# SparkoStat.net
KiCad netlist of a schematic drawn in EAGLE
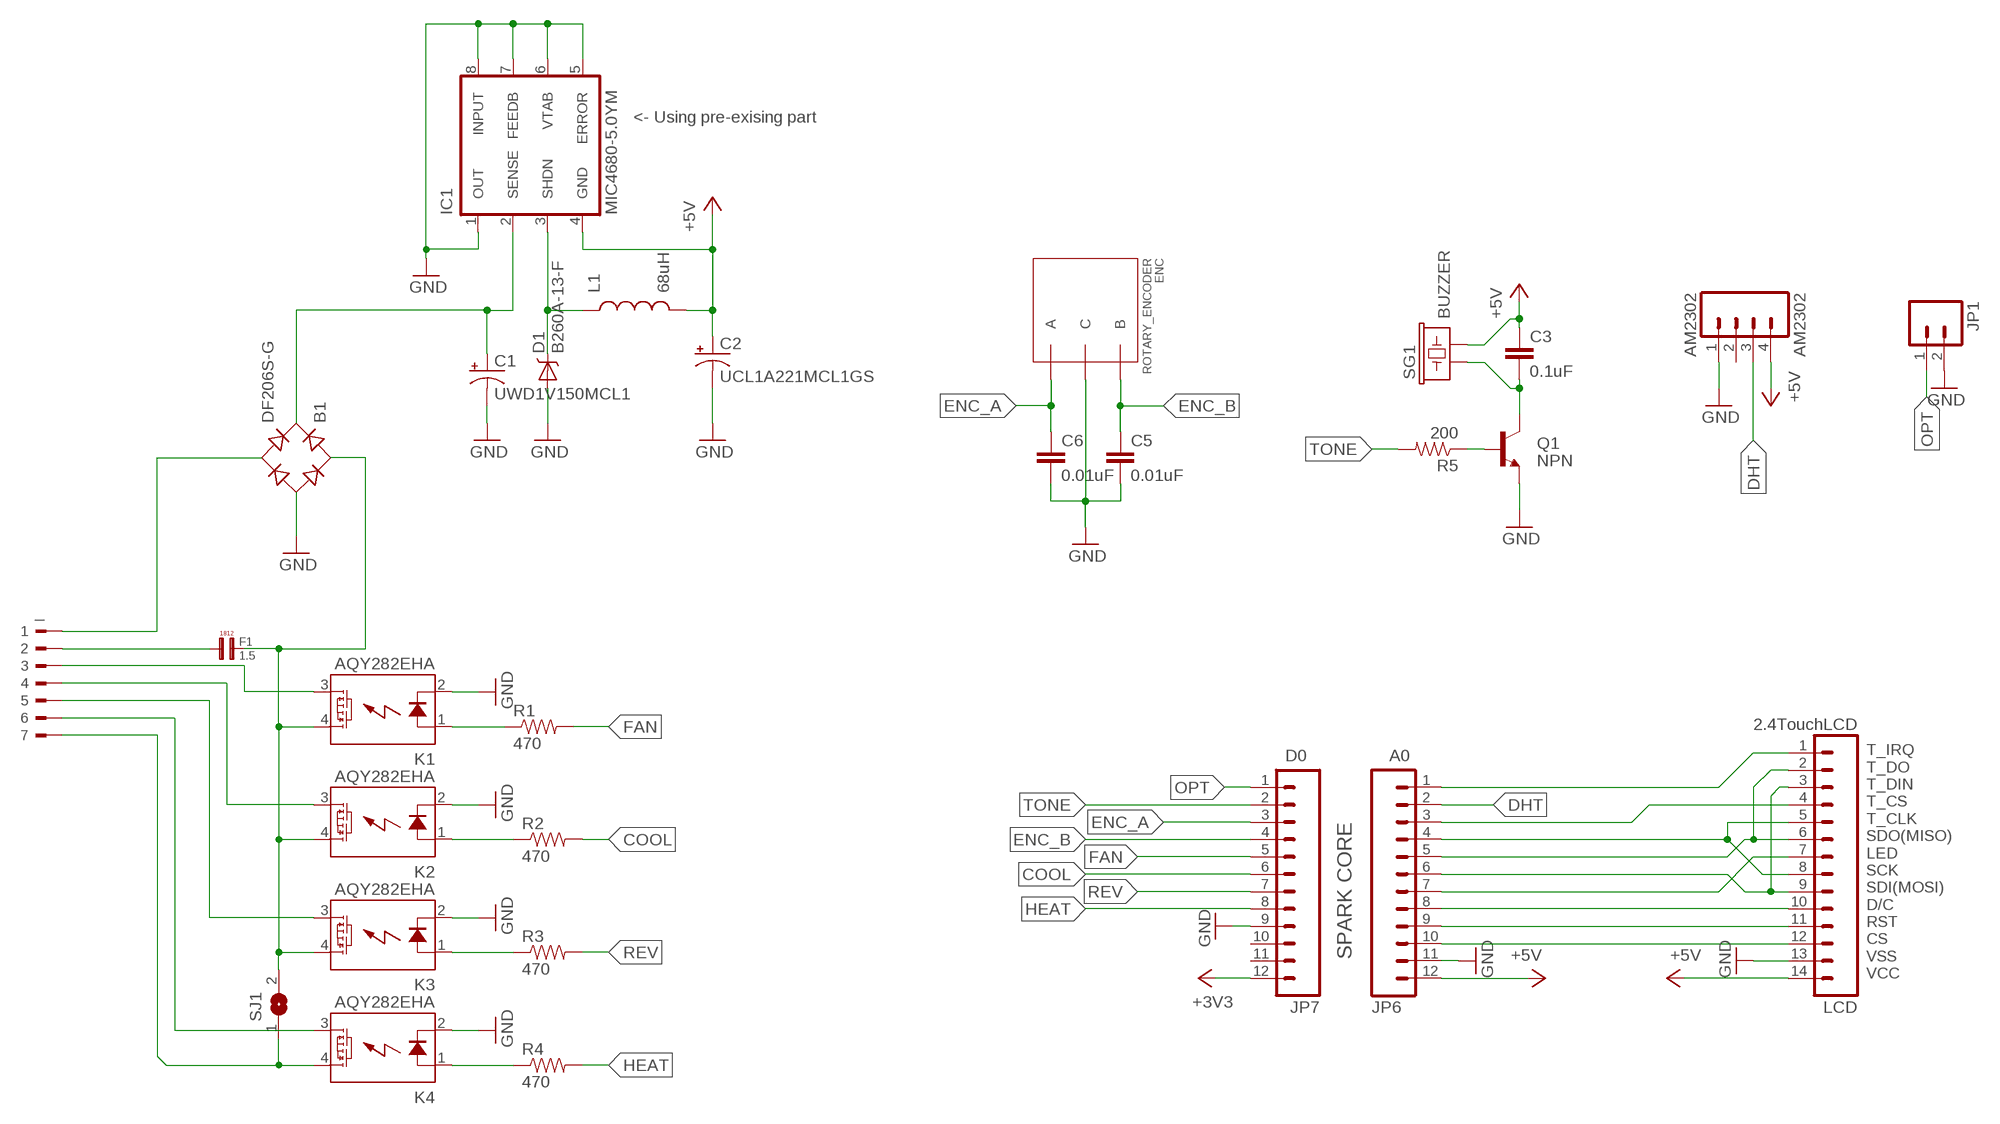
[diagram p0: schematic, sheet 1]

(export (version "E")
  (design (tool "Eeschema 10.0.6"))
  (components
    (comp (ref "AM2302")
      (value "AM2302")
      (footprint "eagle-import:1X04")
      (libsource (lib "eagle-import") (part "M04PTH"))
    )
    (comp (ref "B1")
      (value "DF206S-G")
      (footprint "eagle-import:DFS")
      (libsource (lib "eagle-import") (part "DFS01"))
    )
    (comp (ref "C1")
      (value "UWD1V150MCL1")
      (footprint "eagle-import:PANASONIC_C")
      (libsource (lib "eagle-import") (part "CAP_POLC"))
    )
    (comp (ref "C2")
      (value "UCL1A221MCL1GS")
      (footprint "eagle-import:PANASONIC_D")
      (libsource (lib "eagle-import") (part "CAP_POLD"))
    )
    (comp (ref "C3")
      (value "0.1uF")
      (footprint "eagle-import:0805")
      (libsource (lib "eagle-import") (part "CAP0805"))
    )
    (comp (ref "C5")
      (value "0.01uF")
      (footprint "eagle-import:0805")
      (libsource (lib "eagle-import") (part "CAP0805"))
    )
    (comp (ref "C6")
      (value "0.01uF")
      (footprint "eagle-import:0805")
      (libsource (lib "eagle-import") (part "CAP0805"))
    )
    (comp (ref "D1")
      (value "B260A-13-F")
      (footprint "eagle-import:SMA-DIODE")
      (libsource (lib "eagle-import") (part "DIODE-SCHOTTKY_"))
    )
    (comp (ref "ENC")
      (value "ROTARY_ENCODER")
      (footprint "eagle-import:ROTORY_ENC")
      (libsource (lib "eagle-import") (part "ROTARY_ENCODER"))
    )
    (comp (ref "F1")
      (value "1.5")
      (footprint "eagle-import:L4,8")
      (libsource (lib "eagle-import") (part "0,1ÂµF"))
    )
    (comp (ref "IC1")
      (value "MIC4680-5.0YM")
      (footprint "eagle-import:SO-08")
      (libsource (lib "eagle-import") (part "LP2951?ACM"))
    )
    (comp (ref "JP1")
      (value "M02PTH")
      (footprint "eagle-import:1X02")
      (libsource (lib "eagle-import") (part "M02PTH"))
    )
    (comp (ref "JP6")
      (value "M12LOCK")
      (footprint "eagle-import:1X12_LOCK")
      (libsource (lib "eagle-import") (part "M12LOCK"))
    )
    (comp (ref "JP7")
      (value "M12LOCK")
      (footprint "eagle-import:1X12_LOCK")
      (libsource (lib "eagle-import") (part "M12LOCK"))
    )
    (comp (ref "K1")
      (value "AQY282EHA")
      (footprint "eagle-import:SOP04")
      (libsource (lib "eagle-import") (part "AQYSOP22"))
    )
    (comp (ref "K2")
      (value "AQY282EHA")
      (footprint "eagle-import:SOP04")
      (libsource (lib "eagle-import") (part "AQYSOP22"))
    )
    (comp (ref "K3")
      (value "AQY282EHA")
      (footprint "eagle-import:SOP04")
      (libsource (lib "eagle-import") (part "AQYSOP22"))
    )
    (comp (ref "K4")
      (value "AQY282EHA")
      (footprint "eagle-import:SOP04")
      (libsource (lib "eagle-import") (part "AQYSOP22"))
    )
    (comp (ref "L1")
      (value "68uH")
      (footprint "eagle-import:DR1030")
      (libsource (lib "eagle-import") (part "INDUCTORDR1030"))
    )
    (comp (ref "LCD")
      (value "2.4TouchLCD")
      (footprint "eagle-import:1X14_LOCK")
      (libsource (lib "eagle-import") (part "M14LOCK"))
    )
    (comp (ref "Q1")
      (value "NPN")
      (footprint "eagle-import:SOT23")
      (libsource (lib "eagle-import") (part "TRANSISTOR_NPNSOT23"))
    )
    (comp (ref "R1")
      (value "470")
      (footprint "eagle-import:0805")
      (libsource (lib "eagle-import") (part "RESISTOR0805-RES"))
    )
    (comp (ref "R2")
      (value "470")
      (footprint "eagle-import:0805")
      (libsource (lib "eagle-import") (part "RESISTOR0805-RES"))
    )
    (comp (ref "R3")
      (value "470")
      (footprint "eagle-import:0805")
      (libsource (lib "eagle-import") (part "RESISTOR0805-RES"))
    )
    (comp (ref "R4")
      (value "470")
      (footprint "eagle-import:0805")
      (libsource (lib "eagle-import") (part "RESISTOR0805-RES"))
    )
    (comp (ref "R5")
      (value "200")
      (footprint "eagle-import:0805")
      (libsource (lib "eagle-import") (part "RESISTOR0805-RES"))
    )
    (comp (ref "SG1")
      (value "BUZZER")
      (footprint "eagle-import:BUZZER-12MM-NS")
      (libsource (lib "eagle-import") (part "BUZZERNS"))
    )
    (comp (ref "SJ1") (value "SJ") (footprint "eagle-import:SJ") (libsource (lib "eagle-import") (part "SJ")))
    (comp (ref "_")
      (value "180-7")
      (footprint "eagle-import:180-7")
      (libsource (lib "eagle-import") (part "180-7"))
    )
  )
  (nets
    (net (code "1") (name "+3V3") (class "Default")
      (node (ref "JP7") (pin "12") (pinfunction "12_12") (pintype "passive"))
    )
    (net (code "2") (name "+5V") (class "Default")
      (node (ref "AM2302") (pin "4") (pinfunction "4_4") (pintype "passive"))
      (node (ref "C2") (pin "+") (pinfunction "+_+") (pintype "passive"))
      (node (ref "C3") (pin "1") (pinfunction "1_1") (pintype "passive"))
      (node (ref "IC1") (pin "4") (pinfunction "GND_4") (pintype "power_in"))
      (node (ref "JP6") (pin "12") (pinfunction "12_12") (pintype "passive"))
      (node (ref "L1") (pin "2") (pinfunction "2_2") (pintype "passive"))
      (node (ref "LCD") (pin "14") (pinfunction "14_14") (pintype "passive"))
      (node (ref "SG1") (pin "-") (pinfunction "2_-") (pintype "passive"))
    )
    (net (code "3") (name "COOL") (class "Default")
      (node (ref "JP7") (pin "6") (pinfunction "6_6") (pintype "passive"))
      (node (ref "R2") (pin "2") (pinfunction "2_2") (pintype "passive"))
    )
    (net (code "4") (name "DHT") (class "Default")
      (node (ref "AM2302") (pin "3") (pinfunction "3_3") (pintype "passive"))
      (node (ref "JP6") (pin "2") (pinfunction "2_2") (pintype "passive"))
    )
    (net (code "5") (name "ENC_A") (class "Default")
      (node (ref "C6") (pin "1") (pinfunction "1_1") (pintype "passive"))
      (node (ref "ENC") (pin "A") (pinfunction "A_A") (pintype "bidirectional"))
      (node (ref "JP7") (pin "3") (pinfunction "3_3") (pintype "passive"))
    )
    (net (code "6") (name "ENC_B") (class "Default")
      (node (ref "C5") (pin "1") (pinfunction "1_1") (pintype "passive"))
      (node (ref "ENC") (pin "B") (pinfunction "B_B") (pintype "bidirectional"))
      (node (ref "JP7") (pin "4") (pinfunction "4_4") (pintype "passive"))
    )
    (net (code "7") (name "FAN") (class "Default")
      (node (ref "JP7") (pin "5") (pinfunction "5_5") (pintype "passive"))
      (node (ref "R1") (pin "2") (pinfunction "2_2") (pintype "passive"))
    )
    (net (code "8") (name "GND") (class "Default")
      (node (ref "AM2302") (pin "1") (pinfunction "1_1") (pintype "passive"))
      (node (ref "B1") (pin "-") (pinfunction "-_-") (pintype "passive"))
      (node (ref "C1") (pin "-") (pinfunction "-_-") (pintype "passive"))
      (node (ref "C2") (pin "-") (pinfunction "-_-") (pintype "passive"))
      (node (ref "C5") (pin "2") (pinfunction "2_2") (pintype "passive"))
      (node (ref "C6") (pin "2") (pinfunction "2_2") (pintype "passive"))
      (node (ref "D1") (pin "A") (pinfunction "A_A") (pintype "passive"))
      (node (ref "ENC") (pin "C") (pinfunction "C_C") (pintype "bidirectional"))
      (node (ref "IC1") (pin "1") (pinfunction "OUT_1") (pintype "output"))
      (node (ref "IC1") (pin "5") (pinfunction "ERROR_5") (pintype "output"))
      (node (ref "IC1") (pin "6") (pinfunction "VTAB_6") (pintype "input"))
      (node (ref "IC1") (pin "7") (pinfunction "FEEDB_7") (pintype "output"))
      (node (ref "IC1") (pin "8") (pinfunction "INPUT_8") (pintype "passive"))
      (node (ref "JP1") (pin "2") (pinfunction "2_2") (pintype "passive"))
      (node (ref "JP6") (pin "11") (pinfunction "11_11") (pintype "passive"))
      (node (ref "JP7") (pin "9") (pinfunction "9_9") (pintype "passive"))
      (node (ref "K1") (pin "2") (pinfunction "K_2") (pintype "passive"))
      (node (ref "K2") (pin "2") (pinfunction "K_2") (pintype "passive"))
      (node (ref "K3") (pin "2") (pinfunction "K_2") (pintype "passive"))
      (node (ref "K4") (pin "2") (pinfunction "K_2") (pintype "passive"))
      (node (ref "LCD") (pin "13") (pinfunction "13_13") (pintype "passive"))
      (node (ref "Q1") (pin "2") (pinfunction "E_2") (pintype "passive"))
    )
    (net (code "9") (name "HEAT") (class "Default")
      (node (ref "JP7") (pin "8") (pinfunction "8_8") (pintype "passive"))
      (node (ref "R4") (pin "2") (pinfunction "2_2") (pintype "passive"))
    )
    (net (code "10") (name "Net-(B1-PadAC2)") (class "Default")
      (node (ref "B1") (pin "AC2") (pinfunction "AC2_AC2") (pintype "passive"))
      (node (ref "_") (pin "1") (pinfunction "1_1") (pintype "passive"))
    )
    (net (code "11") (name "Net-(F1-1)") (class "Default")
      (node (ref "F1") (pin "P$1") (pinfunction "1_P$1") (pintype "passive"))
      (node (ref "_") (pin "2") (pinfunction "2_2") (pintype "passive"))
    )
    (net (code "12") (name "Net-(F1-2)") (class "Default")
      (node (ref "B1") (pin "AC1") (pinfunction "AC1_AC1") (pintype "passive"))
      (node (ref "F1") (pin "P$2") (pinfunction "2_P$2") (pintype "passive"))
      (node (ref "K1") (pin "4") (pinfunction "DS1_4") (pintype "passive"))
      (node (ref "K2") (pin "4") (pinfunction "DS1_4") (pintype "passive"))
      (node (ref "K3") (pin "4") (pinfunction "DS1_4") (pintype "passive"))
      (node (ref "SJ1") (pin "2") (pinfunction "2_2") (pintype "passive"))
    )
    (net (code "13") (name "Net-(IC1-SENSE)") (class "Default")
      (node (ref "B1") (pin "+") (pinfunction "+_+") (pintype "passive"))
      (node (ref "C1") (pin "+") (pinfunction "+_+") (pintype "passive"))
      (node (ref "IC1") (pin "2") (pinfunction "SENSE_2") (pintype "input"))
    )
    (net (code "14") (name "Net-(IC1-SHDN)") (class "Default")
      (node (ref "D1") (pin "C") (pinfunction "C_C") (pintype "passive"))
      (node (ref "IC1") (pin "3") (pinfunction "SHDN_3") (pintype "input"))
      (node (ref "L1") (pin "1") (pinfunction "1_1") (pintype "passive"))
    )
    (net (code "15") (name "Net-(JP6-Pad1)") (class "Default")
      (node (ref "JP6") (pin "1") (pinfunction "1_1") (pintype "passive"))
      (node (ref "LCD") (pin "1") (pinfunction "1_1") (pintype "passive"))
    )
    (net (code "16") (name "Net-(JP6-Pad3)") (class "Default")
      (node (ref "JP6") (pin "3") (pinfunction "3_3") (pintype "passive"))
      (node (ref "LCD") (pin "4") (pinfunction "4_4") (pintype "passive"))
    )
    (net (code "17") (name "Net-(JP6-Pad4)") (class "Default")
      (node (ref "JP6") (pin "4") (pinfunction "4_4") (pintype "passive"))
      (node (ref "LCD") (pin "5") (pinfunction "5_5") (pintype "passive"))
      (node (ref "LCD") (pin "8") (pinfunction "8_8") (pintype "passive"))
    )
    (net (code "18") (name "Net-(JP6-Pad5)") (class "Default")
      (node (ref "JP6") (pin "5") (pinfunction "5_5") (pintype "passive"))
      (node (ref "LCD") (pin "2") (pinfunction "2_2") (pintype "passive"))
      (node (ref "LCD") (pin "6") (pinfunction "6_6") (pintype "passive"))
    )
    (net (code "19") (name "Net-(JP6-Pad6)") (class "Default")
      (node (ref "JP6") (pin "6") (pinfunction "6_6") (pintype "passive"))
      (node (ref "LCD") (pin "3") (pinfunction "3_3") (pintype "passive"))
      (node (ref "LCD") (pin "9") (pinfunction "9_9") (pintype "passive"))
    )
    (net (code "20") (name "Net-(JP6-Pad7)") (class "Default")
      (node (ref "JP6") (pin "7") (pinfunction "7_7") (pintype "passive"))
      (node (ref "LCD") (pin "7") (pinfunction "7_7") (pintype "passive"))
    )
    (net (code "21") (name "Net-(JP6-Pad8)") (class "Default")
      (node (ref "JP6") (pin "8") (pinfunction "8_8") (pintype "passive"))
      (node (ref "LCD") (pin "10") (pinfunction "10_10") (pintype "passive"))
    )
    (net (code "22") (name "Net-(JP6-Pad9)") (class "Default")
      (node (ref "JP6") (pin "9") (pinfunction "9_9") (pintype "passive"))
      (node (ref "LCD") (pin "11") (pinfunction "11_11") (pintype "passive"))
    )
    (net (code "23") (name "Net-(JP6-Pad10)") (class "Default")
      (node (ref "JP6") (pin "10") (pinfunction "10_10") (pintype "passive"))
      (node (ref "LCD") (pin "12") (pinfunction "12_12") (pintype "passive"))
    )
    (net (code "24") (name "Net-(K1-A)") (class "Default")
      (node (ref "K1") (pin "1") (pinfunction "A_1") (pintype "passive"))
      (node (ref "R1") (pin "1") (pinfunction "1_1") (pintype "passive"))
    )
    (net (code "25") (name "Net-(K1-DS2)") (class "Default")
      (node (ref "K1") (pin "3") (pinfunction "DS2_3") (pintype "passive"))
      (node (ref "_") (pin "3") (pinfunction "3_3") (pintype "passive"))
    )
    (net (code "26") (name "Net-(K2-A)") (class "Default")
      (node (ref "K2") (pin "1") (pinfunction "A_1") (pintype "passive"))
      (node (ref "R2") (pin "1") (pinfunction "1_1") (pintype "passive"))
    )
    (net (code "27") (name "Net-(K2-DS2)") (class "Default")
      (node (ref "K2") (pin "3") (pinfunction "DS2_3") (pintype "passive"))
      (node (ref "_") (pin "4") (pinfunction "4_4") (pintype "passive"))
    )
    (net (code "28") (name "Net-(K3-A)") (class "Default")
      (node (ref "K3") (pin "1") (pinfunction "A_1") (pintype "passive"))
      (node (ref "R3") (pin "1") (pinfunction "1_1") (pintype "passive"))
    )
    (net (code "29") (name "Net-(K3-DS2)") (class "Default")
      (node (ref "K3") (pin "3") (pinfunction "DS2_3") (pintype "passive"))
      (node (ref "_") (pin "5") (pinfunction "5_5") (pintype "passive"))
    )
    (net (code "30") (name "Net-(K4-A)") (class "Default")
      (node (ref "K4") (pin "1") (pinfunction "A_1") (pintype "passive"))
      (node (ref "R4") (pin "1") (pinfunction "1_1") (pintype "passive"))
    )
    (net (code "31") (name "Net-(K4-DS1)") (class "Default")
      (node (ref "K4") (pin "4") (pinfunction "DS1_4") (pintype "passive"))
      (node (ref "SJ1") (pin "1") (pinfunction "1_1") (pintype "passive"))
      (node (ref "_") (pin "7") (pinfunction "7_7") (pintype "passive"))
    )
    (net (code "32") (name "Net-(K4-DS2)") (class "Default")
      (node (ref "K4") (pin "3") (pinfunction "DS2_3") (pintype "passive"))
      (node (ref "_") (pin "6") (pinfunction "6_6") (pintype "passive"))
    )
    (net (code "33") (name "Net-(Q1-B)") (class "Default")
      (node (ref "Q1") (pin "1") (pinfunction "B_1") (pintype "passive"))
      (node (ref "R5") (pin "1") (pinfunction "1_1") (pintype "passive"))
    )
    (net (code "34") (name "Net-(Q1-C)") (class "Default")
      (node (ref "C3") (pin "2") (pinfunction "2_2") (pintype "passive"))
      (node (ref "Q1") (pin "3") (pinfunction "C_3") (pintype "passive"))
      (node (ref "SG1") (pin "+") (pinfunction "1_+") (pintype "passive"))
    )
    (net (code "35") (name "OPT") (class "Default")
      (node (ref "JP1") (pin "1") (pinfunction "1_1") (pintype "passive"))
      (node (ref "JP7") (pin "1") (pinfunction "1_1") (pintype "passive"))
    )
    (net (code "36") (name "REV") (class "Default")
      (node (ref "JP7") (pin "7") (pinfunction "7_7") (pintype "passive"))
      (node (ref "R3") (pin "2") (pinfunction "2_2") (pintype "passive"))
    )
    (net (code "37") (name "TONE") (class "Default")
      (node (ref "JP7") (pin "2") (pinfunction "2_2") (pintype "passive"))
      (node (ref "R5") (pin "2") (pinfunction "2_2") (pintype "passive"))
    )
    (net (code "38") (name "unconnected-(AM2302-Pad2)") (class "Default")
      (node (ref "AM2302") (pin "2") (pinfunction "2_2") (pintype "passive"))
    )
    (net (code "39") (name "unconnected-(JP7-Pad10)") (class "Default")
      (node (ref "JP7") (pin "10") (pinfunction "10_10") (pintype "passive"))
    )
    (net (code "40") (name "unconnected-(JP7-Pad11)") (class "Default")
      (node (ref "JP7") (pin "11") (pinfunction "11_11") (pintype "passive"))
    )
  )
)
